# DomBoard.net
KiCad netlist of a schematic drawn in EAGLE
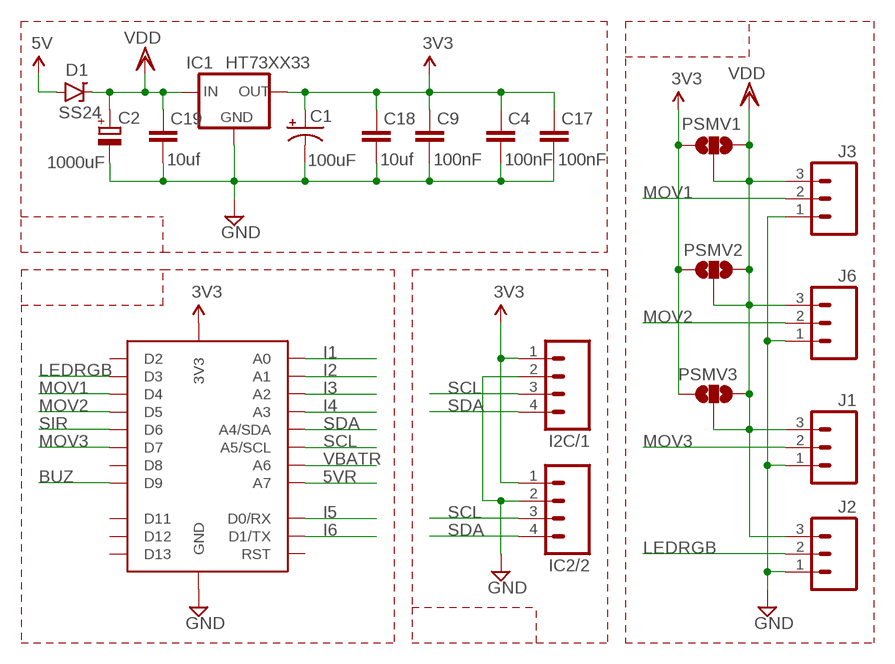
[diagram p0: schematic, sheet 1]
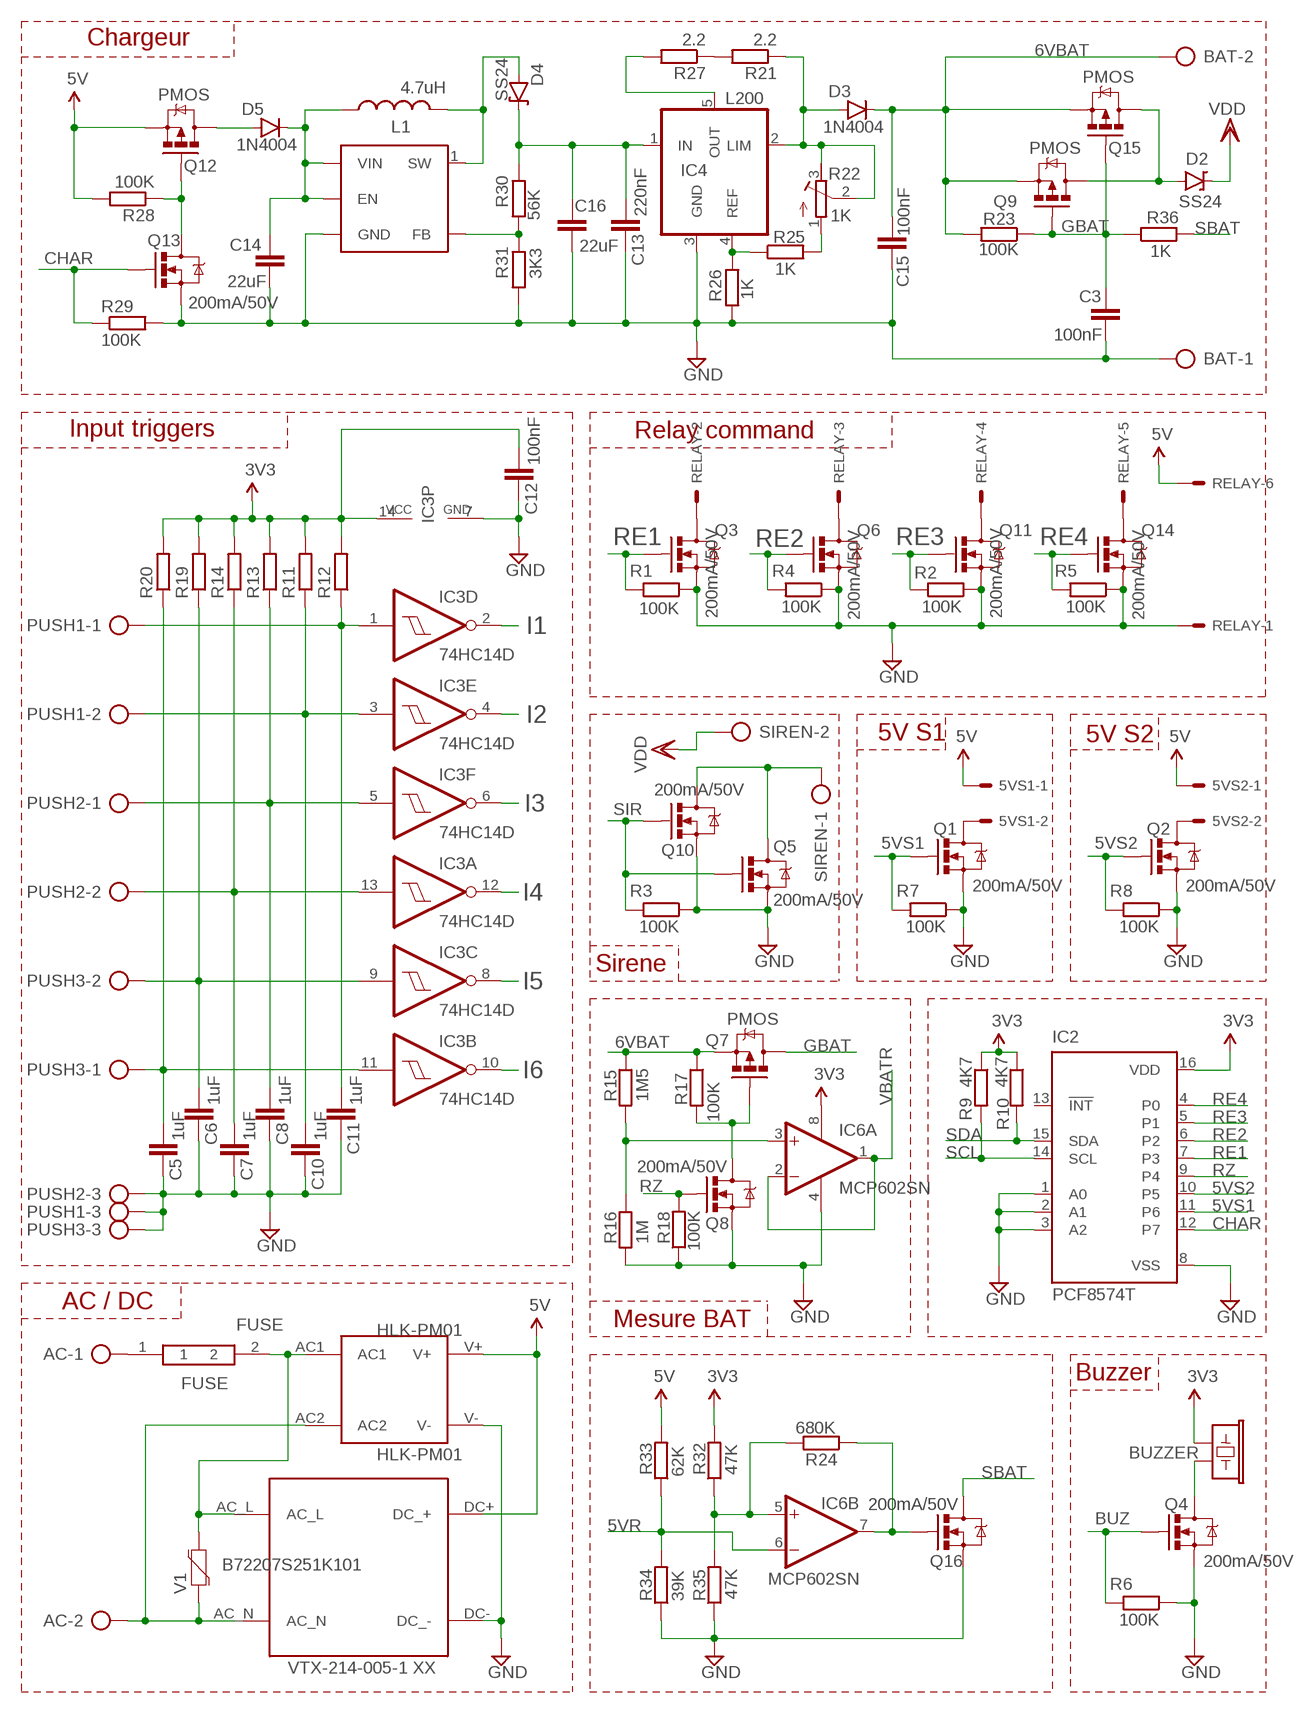
[diagram p1: schematic, sheet 2]

(export (version "E")
  (design (tool "Eeschema 10.0.6"))
  (components
    (comp (ref "C1")
      (value "100uF")
      (footprint "eagle-import:EIA3528-KIT")
      (libsource (lib "eagle-import") (part "CAP_POL3528-KIT"))
    )
    (comp (ref "C2")
      (value "1000uF")
      (footprint "eagle-import:E5-8,5")
      (libsource (lib "eagle-import") (part "CPOL-EUE5-8.5"))
    )
    (comp (ref "C4")
      (value "100nF")
      (footprint "eagle-import:C0805K")
      (libsource (lib "eagle-import") (part "C-EUC0805K"))
    )
    (comp (ref "C9")
      (value "100nF")
      (footprint "eagle-import:C0805K")
      (libsource (lib "eagle-import") (part "C-EUC0805K"))
    )
    (comp (ref "C17")
      (value "100nF")
      (footprint "eagle-import:C0805K")
      (libsource (lib "eagle-import") (part "C-EUC0805K"))
    )
    (comp (ref "C18")
      (value "10uf")
      (footprint "eagle-import:C0805K")
      (libsource (lib "eagle-import") (part "C-EUC0805K"))
    )
    (comp (ref "C19")
      (value "10uf")
      (footprint "eagle-import:C0805K")
      (libsource (lib "eagle-import") (part "C-EUC0805K"))
    )
    (comp (ref "D1")
      (value "SS24")
      (footprint "eagle-import:DO-214AA(1)")
      (libsource (lib "eagle-import") (part "SS24"))
    )
    (comp (ref "I2C/1")
      (value "M04PTH")
      (footprint "eagle-import:1X04")
      (libsource (lib "eagle-import") (part "M04PTH"))
    )
    (comp (ref "IC1")
      (value "HT73XX33")
      (footprint "eagle-import:SOT-89")
      (libsource (lib "eagle-import") (part "HT73XX33"))
    )
    (comp (ref "IC2/2")
      (value "M04PTH")
      (footprint "eagle-import:1X04")
      (libsource (lib "eagle-import") (part "M04PTH"))
    )
    (comp (ref "J1")
      (value "M03JST-PTH-VERT")
      (footprint "eagle-import:JST-3-PTH-VERT")
      (libsource (lib "eagle-import") (part "M03JST-PTH-VERT"))
    )
    (comp (ref "J2")
      (value "M03JST-PTH-VERT")
      (footprint "eagle-import:JST-3-PTH-VERT")
      (libsource (lib "eagle-import") (part "M03JST-PTH-VERT"))
    )
    (comp (ref "J3")
      (value "M03JST-PTH-VERT")
      (footprint "eagle-import:JST-3-PTH-VERT")
      (libsource (lib "eagle-import") (part "M03JST-PTH-VERT"))
    )
    (comp (ref "J6")
      (value "M03JST-PTH-VERT")
      (footprint "eagle-import:JST-3-PTH-VERT")
      (libsource (lib "eagle-import") (part "M03JST-PTH-VERT"))
    )
    (comp (ref "PROMINI69")
      (value "PROMINI69")
      (footprint "eagle-import:PROMINI69")
      (libsource (lib "eagle-import") (part "PROMINI69"))
    )
    (comp (ref "PSMV1")
      (value "JUMPER-PAD-3-NC_BY_TRACE")
      (footprint "eagle-import:PAD-JUMPER-3-3OF3_NC_BY_TRACE_YES_SILK_FULL_BOX")
      (libsource (lib "eagle-import") (part "JUMPER-PAD-3-NC_BY_TRACE"))
    )
    (comp (ref "PSMV2")
      (value "JUMPER-PAD-3-NC_BY_TRACE")
      (footprint "eagle-import:PAD-JUMPER-3-3OF3_NC_BY_TRACE_YES_SILK_FULL_BOX")
      (libsource (lib "eagle-import") (part "JUMPER-PAD-3-NC_BY_TRACE"))
    )
    (comp (ref "PSMV3")
      (value "JUMPER-PAD-3-NC_BY_TRACE")
      (footprint "eagle-import:PAD-JUMPER-3-3OF3_NC_BY_TRACE_YES_SILK_FULL_BOX")
      (libsource (lib "eagle-import") (part "JUMPER-PAD-3-NC_BY_TRACE"))
    )
    (comp (ref "5VS1")
      (value "22-23-2021")
      (footprint "eagle-import:22-23-2021")
      (fields (field (name "MF") "MOLEX"))
      (libsource (lib "eagle-import") (part "22-23-2021"))
    )
    (comp (ref "5VS2")
      (value "22-23-2021")
      (footprint "eagle-import:22-23-2021")
      (fields (field (name "MF") "MOLEX"))
      (libsource (lib "eagle-import") (part "22-23-2021"))
    )
    (comp (ref "AC")
      (value "AK500/2")
      (footprint "eagle-import:AK500_2")
      (libsource (lib "eagle-import") (part "AK500/2"))
    )
    (comp (ref "BAT")
      (value "AK500/2")
      (footprint "eagle-import:AK500_2")
      (libsource (lib "eagle-import") (part "AK500/2"))
    )
    (comp (ref "BUZZER")
      (value "BUZZER")
      (footprint "eagle-import:BUZZER-12MM")
      (libsource (lib "eagle-import") (part "BUZZERPTH"))
    )
    (comp (ref "C3")
      (value "100nF")
      (footprint "eagle-import:C0805K")
      (libsource (lib "eagle-import") (part "C-EUC0805K"))
    )
    (comp (ref "C5")
      (value "1uF")
      (footprint "eagle-import:C0805K")
      (libsource (lib "eagle-import") (part "C-EUC0805K"))
    )
    (comp (ref "C6")
      (value "1uF")
      (footprint "eagle-import:C0805K")
      (libsource (lib "eagle-import") (part "C-EUC0805K"))
    )
    (comp (ref "C7")
      (value "1uF")
      (footprint "eagle-import:C0805K")
      (libsource (lib "eagle-import") (part "C-EUC0805K"))
    )
    (comp (ref "C8")
      (value "1uF")
      (footprint "eagle-import:C0805K")
      (libsource (lib "eagle-import") (part "C-EUC0805K"))
    )
    (comp (ref "C10")
      (value "1uF")
      (footprint "eagle-import:C0805K")
      (libsource (lib "eagle-import") (part "C-EUC0805K"))
    )
    (comp (ref "C11")
      (value "1uF")
      (footprint "eagle-import:C0805K")
      (libsource (lib "eagle-import") (part "C-EUC0805K"))
    )
    (comp (ref "C12")
      (value "100nF")
      (footprint "eagle-import:C0805K")
      (libsource (lib "eagle-import") (part "C-EUC0805K"))
    )
    (comp (ref "C13")
      (value "220nF")
      (footprint "eagle-import:C0805K")
      (libsource (lib "eagle-import") (part "C-EUC0805K"))
    )
    (comp (ref "C14")
      (value "22uF")
      (footprint "eagle-import:C0805K")
      (libsource (lib "eagle-import") (part "C-EUC0805K"))
    )
    (comp (ref "C15")
      (value "100nF")
      (footprint "eagle-import:C0805K")
      (libsource (lib "eagle-import") (part "C-EUC0805K"))
    )
    (comp (ref "C16")
      (value "22uF")
      (footprint "eagle-import:C0805K")
      (libsource (lib "eagle-import") (part "C-EUC0805K"))
    )
    (comp (ref "D2")
      (value "SS24")
      (footprint "eagle-import:DO-214AA(1)")
      (libsource (lib "eagle-import") (part "SS24"))
    )
    (comp (ref "D3")
      (value "1N4004")
      (footprint "eagle-import:DO-214AA(1)")
      (libsource (lib "eagle-import") (part "DIODE"))
    )
    (comp (ref "D4")
      (value "SS24")
      (footprint "eagle-import:DO-214AA(1)")
      (libsource (lib "eagle-import") (part "SS24"))
    )
    (comp (ref "D5")
      (value "1N4004")
      (footprint "eagle-import:DO-214AA(1)")
      (libsource (lib "eagle-import") (part "DIODE"))
    )
    (comp (ref "FUSE")
      (value "FUSE")
      (footprint "eagle-import:FUSE_BEL_RST5_5A")
      (libsource (lib "eagle-import") (part "FUSE"))
    )
    (comp (ref "HLK-PM01")
      (value "HLK-PM01")
      (footprint "eagle-import:HILINK_HLK-PM01")
      (libsource (lib "eagle-import") (part "HILINK_HLK-PM01"))
    )
    (comp (ref "IC2")
      (value "PCF8574T")
      (footprint "eagle-import:SO16W")
      (fields (field (name "MPN") "PCF8574T/3,512"))
      (libsource (lib "eagle-import") (part "PCF8574T"))
    )
    (comp (ref "IC3")
      (value "74HC14D")
      (footprint "eagle-import:SO14")
      (libsource (lib "eagle-import") (part "7414DHC"))
    )
    (comp (ref "IC4")
      (value "L200")
      (footprint "eagle-import:L200S")
      (libsource (lib "eagle-import") (part "L200"))
    )
    (comp (ref "IC5")
      (value "SX1308")
      (footprint "eagle-import:SOT23-6")
      (libsource (lib "eagle-import") (part "SX1308"))
    )
    (comp (ref "IC6")
      (value "MCP602SN")
      (footprint "eagle-import:SO08")
      (libsource (lib "eagle-import") (part "MCP602SN"))
    )
    (comp (ref "L1")
      (value "4.7uH")
      (footprint "eagle-import:INDUC1")
      (libsource (lib "eagle-import") (part "INDUCTOR"))
    )
    (comp (ref "PUSH1")
      (value "AK500/3")
      (footprint "eagle-import:AK500_3")
      (libsource (lib "eagle-import") (part "AK500/3"))
    )
    (comp (ref "PUSH2")
      (value "AK500/3")
      (footprint "eagle-import:AK500_3")
      (libsource (lib "eagle-import") (part "AK500/3"))
    )
    (comp (ref "PUSH3")
      (value "AK500/3")
      (footprint "eagle-import:AK500_3")
      (libsource (lib "eagle-import") (part "AK500/3"))
    )
    (comp (ref "Q1")
      (value "200mA/50V")
      (footprint "eagle-import:SOT23-3")
      (libsource (lib "eagle-import") (part "N-MOSFETBSS138"))
    )
    (comp (ref "Q2")
      (value "200mA/50V")
      (footprint "eagle-import:SOT23-3")
      (libsource (lib "eagle-import") (part "N-MOSFETBSS138"))
    )
    (comp (ref "Q3")
      (value "200mA/50V")
      (footprint "eagle-import:SOT23-3")
      (libsource (lib "eagle-import") (part "N-MOSFETBSS138"))
    )
    (comp (ref "Q4")
      (value "200mA/50V")
      (footprint "eagle-import:SOT23-3")
      (libsource (lib "eagle-import") (part "N-MOSFETBSS138"))
    )
    (comp (ref "Q5")
      (value "200mA/50V")
      (footprint "eagle-import:SOT23-3")
      (libsource (lib "eagle-import") (part "N-MOSFETBSS138"))
    )
    (comp (ref "Q6")
      (value "200mA/50V")
      (footprint "eagle-import:SOT23-3")
      (libsource (lib "eagle-import") (part "N-MOSFETBSS138"))
    )
    (comp (ref "Q7")
      (value "PMOS")
      (footprint "eagle-import:SOT23-3")
      (libsource (lib "eagle-import") (part "P-MOSFET"))
    )
    (comp (ref "Q8")
      (value "200mA/50V")
      (footprint "eagle-import:SOT23-3")
      (libsource (lib "eagle-import") (part "N-MOSFETBSS138"))
    )
    (comp (ref "Q9")
      (value "PMOS")
      (footprint "eagle-import:SOT23-3")
      (libsource (lib "eagle-import") (part "P-MOSFET"))
    )
    (comp (ref "Q10")
      (value "200mA/50V")
      (footprint "eagle-import:SOT23-3")
      (libsource (lib "eagle-import") (part "N-MOSFETBSS138"))
    )
    (comp (ref "Q11")
      (value "200mA/50V")
      (footprint "eagle-import:SOT23-3")
      (libsource (lib "eagle-import") (part "N-MOSFETBSS138"))
    )
    (comp (ref "Q12")
      (value "PMOS")
      (footprint "eagle-import:SOT23-3")
      (libsource (lib "eagle-import") (part "P-MOSFET"))
    )
    (comp (ref "Q13")
      (value "200mA/50V")
      (footprint "eagle-import:SOT23-3")
      (libsource (lib "eagle-import") (part "N-MOSFETBSS138"))
    )
    (comp (ref "Q14")
      (value "200mA/50V")
      (footprint "eagle-import:SOT23-3")
      (libsource (lib "eagle-import") (part "N-MOSFETBSS138"))
    )
    (comp (ref "Q15")
      (value "PMOS")
      (footprint "eagle-import:SOT23-3")
      (libsource (lib "eagle-import") (part "P-MOSFET"))
    )
    (comp (ref "Q16")
      (value "200mA/50V")
      (footprint "eagle-import:SOT23-3")
      (libsource (lib "eagle-import") (part "N-MOSFETBSS138"))
    )
    (comp (ref "R1")
      (value "100K")
      (footprint "eagle-import:R0805")
      (libsource (lib "eagle-import") (part "R-EUR0805"))
    )
    (comp (ref "R2")
      (value "100K")
      (footprint "eagle-import:R0805")
      (libsource (lib "eagle-import") (part "R-EUR0805"))
    )
    (comp (ref "R3")
      (value "100K")
      (footprint "eagle-import:R0805")
      (libsource (lib "eagle-import") (part "R-EUR0805"))
    )
    (comp (ref "R4")
      (value "100K")
      (footprint "eagle-import:R0805")
      (libsource (lib "eagle-import") (part "R-EUR0805"))
    )
    (comp (ref "R5")
      (value "100K")
      (footprint "eagle-import:R0805")
      (libsource (lib "eagle-import") (part "R-EUR0805"))
    )
    (comp (ref "R6")
      (value "100K")
      (footprint "eagle-import:R0805")
      (libsource (lib "eagle-import") (part "R-EUR0805"))
    )
    (comp (ref "R7")
      (value "100K")
      (footprint "eagle-import:R0805")
      (libsource (lib "eagle-import") (part "R-EUR0805"))
    )
    (comp (ref "R8")
      (value "100K")
      (footprint "eagle-import:R0805")
      (libsource (lib "eagle-import") (part "R-EUR0805"))
    )
    (comp (ref "R9")
      (value "4K7")
      (footprint "eagle-import:R0805")
      (libsource (lib "eagle-import") (part "R-EUR0805"))
    )
    (comp (ref "R10")
      (value "4K7")
      (footprint "eagle-import:R0805")
      (libsource (lib "eagle-import") (part "R-EUR0805"))
    )
    (comp (ref "R11")
      (value "R-EUR0805")
      (footprint "eagle-import:R0805")
      (libsource (lib "eagle-import") (part "R-EUR0805"))
    )
    (comp (ref "R12")
      (value "R-EUR0805")
      (footprint "eagle-import:R0805")
      (libsource (lib "eagle-import") (part "R-EUR0805"))
    )
    (comp (ref "R13")
      (value "R-EUR0805")
      (footprint "eagle-import:R0805")
      (libsource (lib "eagle-import") (part "R-EUR0805"))
    )
    (comp (ref "R14")
      (value "R-EUR0805")
      (footprint "eagle-import:R0805")
      (libsource (lib "eagle-import") (part "R-EUR0805"))
    )
    (comp (ref "R15")
      (value "1M5")
      (footprint "eagle-import:R0805")
      (libsource (lib "eagle-import") (part "R-EUR0805"))
    )
    (comp (ref "R16")
      (value "1M")
      (footprint "eagle-import:R0805")
      (libsource (lib "eagle-import") (part "R-EUR0805"))
    )
    (comp (ref "R17")
      (value "100K")
      (footprint "eagle-import:R0805")
      (libsource (lib "eagle-import") (part "R-EUR0805"))
    )
    (comp (ref "R18")
      (value "100K")
      (footprint "eagle-import:R0805")
      (libsource (lib "eagle-import") (part "R-EUR0805"))
    )
    (comp (ref "R19")
      (value "R-EUR0805")
      (footprint "eagle-import:R0805")
      (libsource (lib "eagle-import") (part "R-EUR0805"))
    )
    (comp (ref "R20")
      (value "R-EUR0805")
      (footprint "eagle-import:R0805")
      (libsource (lib "eagle-import") (part "R-EUR0805"))
    )
    (comp (ref "R21")
      (value "2.2")
      (footprint "eagle-import:R0805")
      (libsource (lib "eagle-import") (part "R-EUR0805"))
    )
    (comp (ref "R22")
      (value "1K")
      (footprint "eagle-import:RTRIM3296W")
      (libsource (lib "eagle-import") (part "R-TRIMM3296W"))
    )
    (comp (ref "R23")
      (value "100K")
      (footprint "eagle-import:R0805")
      (libsource (lib "eagle-import") (part "R-EUR0805"))
    )
    (comp (ref "R24")
      (value "680K")
      (footprint "eagle-import:R0805")
      (libsource (lib "eagle-import") (part "R-EUR0805"))
    )
    (comp (ref "R25")
      (value "1K")
      (footprint "eagle-import:R0805")
      (libsource (lib "eagle-import") (part "R-EUR0805"))
    )
    (comp (ref "R26")
      (value "1K")
      (footprint "eagle-import:R0805")
      (libsource (lib "eagle-import") (part "R-EUR0805"))
    )
    (comp (ref "R27")
      (value "2.2")
      (footprint "eagle-import:R0805")
      (libsource (lib "eagle-import") (part "R-EUR0805"))
    )
    (comp (ref "R28")
      (value "100K")
      (footprint "eagle-import:R0805")
      (libsource (lib "eagle-import") (part "R-EUR0805"))
    )
    (comp (ref "R29")
      (value "100K")
      (footprint "eagle-import:R0805")
      (libsource (lib "eagle-import") (part "R-EUR0805"))
    )
    (comp (ref "R30")
      (value "56K")
      (footprint "eagle-import:M0805")
      (libsource (lib "eagle-import") (part "R-EUM0805"))
    )
    (comp (ref "R31")
      (value "3K3")
      (footprint "eagle-import:M0805")
      (libsource (lib "eagle-import") (part "R-EUM0805"))
    )
    (comp (ref "R32")
      (value "47K")
      (footprint "eagle-import:R0805")
      (libsource (lib "eagle-import") (part "R-EUR0805"))
    )
    (comp (ref "R33")
      (value "62K")
      (footprint "eagle-import:R0805")
      (libsource (lib "eagle-import") (part "R-EUR0805"))
    )
    (comp (ref "R34")
      (value "39K")
      (footprint "eagle-import:R0805")
      (libsource (lib "eagle-import") (part "R-EUR0805"))
    )
    (comp (ref "R35")
      (value "47K")
      (footprint "eagle-import:R0805")
      (libsource (lib "eagle-import") (part "R-EUR0805"))
    )
    (comp (ref "R36")
      (value "1K")
      (footprint "eagle-import:R0805")
      (libsource (lib "eagle-import") (part "R-EUR0805"))
    )
    (comp (ref "RELAY")
      (value "22-23-2061")
      (footprint "eagle-import:22-23-2061")
      (fields (field (name "MF") "MOLEX"))
      (libsource (lib "eagle-import") (part "22-23-2061"))
    )
    (comp (ref "SIREN")
      (value "AK500/2")
      (footprint "eagle-import:AK500_2")
      (libsource (lib "eagle-import") (part "AK500/2"))
    )
    (comp (ref "V1")
      (value "B72207S251K101")
      (footprint "eagle-import:VARISTOR_B72207S251K101")
      (libsource (lib "eagle-import") (part "VARISTOR_B72207S251K101"))
    )
    (comp (ref "VTX1")
      (value "VTX-214-005-1XX")
      (footprint "eagle-import:VTX-214-005-1XX")
      (libsource (lib "eagle-import") (part "VTX-214-005-1XX"))
    )
  )
  (nets
    (net (code "1") (name "3.3V") (class "Default")
      (node (ref "BUZZER") (pin "+") (pinfunction "1_+") (pintype "passive"))
      (node (ref "C1") (pin "A") (pinfunction "+_A") (pintype "passive"))
      (node (ref "C12") (pin "1") (pinfunction "1_1") (pintype "passive"))
      (node (ref "C17") (pin "2") (pinfunction "2_2") (pintype "passive"))
      (node (ref "C18") (pin "2") (pinfunction "2_2") (pintype "passive"))
      (node (ref "C4") (pin "2") (pinfunction "2_2") (pintype "passive"))
      (node (ref "C9") (pin "2") (pinfunction "2_2") (pintype "passive"))
      (node (ref "I2C/1") (pin "1") (pinfunction "1_1") (pintype "passive"))
      (node (ref "IC1") (pin "1") (pinfunction "OUT_1") (pintype "passive"))
      (node (ref "IC2") (pin "16") (pinfunction "VDD_16") (pintype "power_in"))
      (node (ref "IC2/2") (pin "1") (pinfunction "1_1") (pintype "passive"))
      (node (ref "IC3") (pin "14") (pinfunction "VCC_14") (pintype "power_in"))
      (node (ref "IC6") (pin "8") (pinfunction "V+_8") (pintype "power_in"))
      (node (ref "PROMINI69") (pin "3V3") (pinfunction "3V3_3V3") (pintype "power_in"))
      (node (ref "PSMV1") (pin "1") (pinfunction "1_1") (pintype "passive"))
      (node (ref "PSMV2") (pin "1") (pinfunction "1_1") (pintype "passive"))
      (node (ref "PSMV3") (pin "1") (pinfunction "1_1") (pintype "passive"))
      (node (ref "R10") (pin "1") (pinfunction "1_1") (pintype "passive"))
      (node (ref "R11") (pin "2") (pinfunction "2_2") (pintype "passive"))
      (node (ref "R12") (pin "2") (pinfunction "2_2") (pintype "passive"))
      (node (ref "R13") (pin "2") (pinfunction "2_2") (pintype "passive"))
      (node (ref "R14") (pin "2") (pinfunction "2_2") (pintype "passive"))
      (node (ref "R19") (pin "2") (pinfunction "2_2") (pintype "passive"))
      (node (ref "R20") (pin "2") (pinfunction "2_2") (pintype "passive"))
      (node (ref "R32") (pin "2") (pinfunction "2_2") (pintype "passive"))
      (node (ref "R9") (pin "1") (pinfunction "1_1") (pintype "passive"))
    )
    (net (code "2") (name "5V") (class "Default")
      (node (ref "5VS1") (pin "1") (pinfunction "S_1") (pintype "passive"))
      (node (ref "5VS2") (pin "1") (pinfunction "S_1") (pintype "passive"))
      (node (ref "D1") (pin "A") (pinfunction "A_A") (pintype "passive"))
      (node (ref "HLK-PM01") (pin "V+") (pinfunction "V+_V+") (pintype "bidirectional"))
      (node (ref "Q12") (pin "2") (pinfunction "S_2") (pintype "passive"))
      (node (ref "R28") (pin "2") (pinfunction "2_2") (pintype "passive"))
      (node (ref "R33") (pin "2") (pinfunction "2_2") (pintype "passive"))
      (node (ref "RELAY") (pin "6") (pinfunction "S_6") (pintype "passive"))
      (node (ref "VTX1") (pin "DC+") (pinfunction "DC_+_DC+") (pintype "power_in"))
    )
    (net (code "3") (name "5VR") (class "Default")
      (node (ref "IC6") (pin "6") (pinfunction "-IN_6") (pintype "input"))
      (node (ref "PROMINI69") (pin "A7") (pinfunction "A7_A7") (pintype "bidirectional"))
      (node (ref "R33") (pin "1") (pinfunction "1_1") (pintype "passive"))
      (node (ref "R34") (pin "2") (pinfunction "2_2") (pintype "passive"))
    )
    (net (code "4") (name "5VS1") (class "Default")
      (node (ref "IC2") (pin "11") (pinfunction "P6_11") (pintype "bidirectional"))
      (node (ref "Q1") (pin "1") (pinfunction "G_1") (pintype "passive"))
      (node (ref "R7") (pin "2") (pinfunction "2_2") (pintype "passive"))
    )
    (net (code "5") (name "5VS2") (class "Default")
      (node (ref "IC2") (pin "10") (pinfunction "P5_10") (pintype "bidirectional"))
      (node (ref "Q2") (pin "1") (pinfunction "G_1") (pintype "passive"))
      (node (ref "R8") (pin "2") (pinfunction "2_2") (pintype "passive"))
    )
    (net (code "6") (name "6VBAT") (class "Default")
      (node (ref "BAT") (pin "2") (pinfunction "KL_2") (pintype "passive"))
      (node (ref "C15") (pin "1") (pinfunction "1_1") (pintype "passive"))
      (node (ref "D3") (pin "C") (pinfunction "C_C") (pintype "passive"))
      (node (ref "Q15") (pin "2") (pinfunction "S_2") (pintype "passive"))
      (node (ref "Q7") (pin "2") (pinfunction "S_2") (pintype "passive"))
      (node (ref "Q9") (pin "2") (pinfunction "S_2") (pintype "passive"))
      (node (ref "R15") (pin "1") (pinfunction "1_1") (pintype "passive"))
      (node (ref "R17") (pin "1") (pinfunction "1_1") (pintype "passive"))
      (node (ref "R23") (pin "2") (pinfunction "2_2") (pintype "passive"))
    )
    (net (code "7") (name "BUZ") (class "Default")
      (node (ref "PROMINI69") (pin "D9") (pinfunction "D9_D9") (pintype "bidirectional"))
      (node (ref "Q4") (pin "1") (pinfunction "G_1") (pintype "passive"))
      (node (ref "R6") (pin "2") (pinfunction "2_2") (pintype "passive"))
    )
    (net (code "8") (name "CHAR") (class "Default")
      (node (ref "IC2") (pin "12") (pinfunction "P7_12") (pintype "bidirectional"))
      (node (ref "Q13") (pin "1") (pinfunction "G_1") (pintype "passive"))
      (node (ref "R29") (pin "1") (pinfunction "1_1") (pintype "passive"))
    )
    (net (code "9") (name "GBAT") (class "Default")
      (node (ref "C3") (pin "1") (pinfunction "1_1") (pintype "passive"))
      (node (ref "Q15") (pin "1") (pinfunction "G_1") (pintype "passive"))
      (node (ref "Q7") (pin "3") (pinfunction "D_3") (pintype "passive"))
      (node (ref "Q9") (pin "1") (pinfunction "G_1") (pintype "passive"))
      (node (ref "R23") (pin "1") (pinfunction "1_1") (pintype "passive"))
      (node (ref "R36") (pin "1") (pinfunction "1_1") (pintype "passive"))
    )
    (net (code "10") (name "GND") (class "Default")
      (node (ref "BAT") (pin "1") (pinfunction "KL_1") (pintype "passive"))
      (node (ref "C1") (pin "C") (pinfunction "-_C") (pintype "passive"))
      (node (ref "C10") (pin "2") (pinfunction "2_2") (pintype "passive"))
      (node (ref "C11") (pin "2") (pinfunction "2_2") (pintype "passive"))
      (node (ref "C12") (pin "2") (pinfunction "2_2") (pintype "passive"))
      (node (ref "C13") (pin "2") (pinfunction "2_2") (pintype "passive"))
      (node (ref "C14") (pin "2") (pinfunction "2_2") (pintype "passive"))
      (node (ref "C15") (pin "2") (pinfunction "2_2") (pintype "passive"))
      (node (ref "C16") (pin "2") (pinfunction "2_2") (pintype "passive"))
      (node (ref "C17") (pin "1") (pinfunction "1_1") (pintype "passive"))
      (node (ref "C18") (pin "1") (pinfunction "1_1") (pintype "passive"))
      (node (ref "C19") (pin "1") (pinfunction "1_1") (pintype "passive"))
      (node (ref "C2") (pin "-") (pinfunction "-_-") (pintype "passive"))
      (node (ref "C3") (pin "2") (pinfunction "2_2") (pintype "passive"))
      (node (ref "C4") (pin "1") (pinfunction "1_1") (pintype "passive"))
      (node (ref "C5") (pin "2") (pinfunction "2_2") (pintype "passive"))
      (node (ref "C6") (pin "2") (pinfunction "2_2") (pintype "passive"))
      (node (ref "C7") (pin "2") (pinfunction "2_2") (pintype "passive"))
      (node (ref "C8") (pin "2") (pinfunction "2_2") (pintype "passive"))
      (node (ref "C9") (pin "1") (pinfunction "1_1") (pintype "passive"))
      (node (ref "HLK-PM01") (pin "V-") (pinfunction "V-_V-") (pintype "bidirectional"))
      (node (ref "I2C/1") (pin "2") (pinfunction "2_2") (pintype "passive"))
      (node (ref "IC1") (pin "2") (pinfunction "GND_2") (pintype "input"))
      (node (ref "IC2") (pin "1") (pinfunction "A0_1") (pintype "input"))
      (node (ref "IC2") (pin "2") (pinfunction "A1_2") (pintype "input"))
      (node (ref "IC2") (pin "3") (pinfunction "A2_3") (pintype "input"))
      (node (ref "IC2") (pin "8") (pinfunction "VSS_8") (pintype "power_in"))
      (node (ref "IC2/2") (pin "2") (pinfunction "2_2") (pintype "passive"))
      (node (ref "IC3") (pin "7") (pinfunction "GND_7") (pintype "power_in"))
      (node (ref "IC4") (pin "3") (pinfunction "GND_3") (pintype "passive"))
      (node (ref "IC5") (pin "2") (pinfunction "GND_2") (pintype "power_in"))
      (node (ref "IC6") (pin "4") (pinfunction "V-_4") (pintype "power_in"))
      (node (ref "J1") (pin "1") (pinfunction "1_1") (pintype "passive"))
      (node (ref "J2") (pin "1") (pinfunction "1_1") (pintype "passive"))
      (node (ref "J3") (pin "1") (pinfunction "1_1") (pintype "passive"))
      (node (ref "J6") (pin "1") (pinfunction "1_1") (pintype "passive"))
      (node (ref "PROMINI69") (pin "GND") (pinfunction "GND_GND") (pintype "power_in"))
      (node (ref "PUSH1") (pin "3") (pinfunction "KL_3") (pintype "passive"))
      (node (ref "PUSH2") (pin "3") (pinfunction "KL_3") (pintype "passive"))
      (node (ref "PUSH3") (pin "3") (pinfunction "KL_3") (pintype "passive"))
      (node (ref "Q1") (pin "2") (pinfunction "S_2") (pintype "passive"))
      (node (ref "Q10") (pin "2") (pinfunction "S_2") (pintype "passive"))
      (node (ref "Q11") (pin "2") (pinfunction "S_2") (pintype "passive"))
      (node (ref "Q13") (pin "2") (pinfunction "S_2") (pintype "passive"))
      (node (ref "Q14") (pin "2") (pinfunction "S_2") (pintype "passive"))
      (node (ref "Q16") (pin "2") (pinfunction "S_2") (pintype "passive"))
      (node (ref "Q2") (pin "2") (pinfunction "S_2") (pintype "passive"))
      (node (ref "Q3") (pin "2") (pinfunction "S_2") (pintype "passive"))
      (node (ref "Q4") (pin "2") (pinfunction "S_2") (pintype "passive"))
      (node (ref "Q5") (pin "2") (pinfunction "S_2") (pintype "passive"))
      (node (ref "Q6") (pin "2") (pinfunction "S_2") (pintype "passive"))
      (node (ref "Q8") (pin "2") (pinfunction "S_2") (pintype "passive"))
      (node (ref "R1") (pin "1") (pinfunction "1_1") (pintype "passive"))
      (node (ref "R16") (pin "2") (pinfunction "2_2") (pintype "passive"))
      (node (ref "R18") (pin "1") (pinfunction "1_1") (pintype "passive"))
      (node (ref "R2") (pin "1") (pinfunction "1_1") (pintype "passive"))
      (node (ref "R26") (pin "2") (pinfunction "2_2") (pintype "passive"))
      (node (ref "R29") (pin "2") (pinfunction "2_2") (pintype "passive"))
      (node (ref "R3") (pin "1") (pinfunction "1_1") (pintype "passive"))
      (node (ref "R31") (pin "1") (pinfunction "1_1") (pintype "passive"))
      (node (ref "R34") (pin "1") (pinfunction "1_1") (pintype "passive"))
      (node (ref "R35") (pin "1") (pinfunction "1_1") (pintype "passive"))
      (node (ref "R4") (pin "1") (pinfunction "1_1") (pintype "passive"))
      (node (ref "R5") (pin "1") (pinfunction "1_1") (pintype "passive"))
      (node (ref "R6") (pin "1") (pinfunction "1_1") (pintype "passive"))
      (node (ref "R7") (pin "1") (pinfunction "1_1") (pintype "passive"))
      (node (ref "R8") (pin "1") (pinfunction "1_1") (pintype "passive"))
      (node (ref "RELAY") (pin "1") (pinfunction "S_1") (pintype "passive"))
      (node (ref "VTX1") (pin "DC-") (pinfunction "DC_-_DC-") (pintype "power_in"))
    )
    (net (code "11") (name "I1") (class "Default")
      (node (ref "IC3") (pin "2") (pinfunction "O_2") (pintype "output"))
      (node (ref "PROMINI69") (pin "A0") (pinfunction "A0_A0") (pintype "bidirectional"))
    )
    (net (code "12") (name "I2") (class "Default")
      (node (ref "IC3") (pin "4") (pinfunction "O_4") (pintype "output"))
      (node (ref "PROMINI69") (pin "A1") (pinfunction "A1_A1") (pintype "bidirectional"))
    )
    (net (code "13") (name "I3") (class "Default")
      (node (ref "IC3") (pin "6") (pinfunction "O_6") (pintype "output"))
      (node (ref "PROMINI69") (pin "A2") (pinfunction "A2_A2") (pintype "bidirectional"))
    )
    (net (code "14") (name "I4") (class "Default")
      (node (ref "IC3") (pin "12") (pinfunction "O_12") (pintype "output"))
      (node (ref "PROMINI69") (pin "A3") (pinfunction "A3_A3") (pintype "bidirectional"))
    )
    (net (code "15") (name "I5") (class "Default")
      (node (ref "IC3") (pin "8") (pinfunction "O_8") (pintype "output"))
      (node (ref "PROMINI69") (pin "D0") (pinfunction "D0/RX_D0") (pintype "bidirectional"))
    )
    (net (code "16") (name "I6") (class "Default")
      (node (ref "IC3") (pin "10") (pinfunction "O_10") (pintype "output"))
      (node (ref "PROMINI69") (pin "D1") (pinfunction "D1/TX_D1") (pintype "bidirectional"))
    )
    (net (code "17") (name "LEDRGB") (class "Default")
      (node (ref "J2") (pin "2") (pinfunction "2_2") (pintype "passive"))
      (node (ref "PROMINI69") (pin "D3") (pinfunction "D3_D3") (pintype "bidirectional"))
    )
    (net (code "18") (name "MOV1") (class "Default")
      (node (ref "J3") (pin "2") (pinfunction "2_2") (pintype "passive"))
      (node (ref "PROMINI69") (pin "D4") (pinfunction "D4_D4") (pintype "bidirectional"))
    )
    (net (code "19") (name "MOV2") (class "Default")
      (node (ref "J6") (pin "2") (pinfunction "2_2") (pintype "passive"))
      (node (ref "PROMINI69") (pin "D5") (pinfunction "D5_D5") (pintype "bidirectional"))
    )
    (net (code "20") (name "MOV3") (class "Default")
      (node (ref "J1") (pin "2") (pinfunction "2_2") (pintype "passive"))
      (node (ref "PROMINI69") (pin "D7") (pinfunction "D7_D7") (pintype "bidirectional"))
    )
    (net (code "21") (name "Net-(5VS1B-S)") (class "Default")
      (node (ref "5VS1") (pin "2") (pinfunction "S_2") (pintype "passive"))
      (node (ref "Q1") (pin "3") (pinfunction "D_3") (pintype "passive"))
    )
    (net (code "22") (name "Net-(5VS2B-S)") (class "Default")
      (node (ref "5VS2") (pin "2") (pinfunction "S_2") (pintype "passive"))
      (node (ref "Q2") (pin "3") (pinfunction "D_3") (pintype "passive"))
    )
    (net (code "23") (name "Net-(ACA-KL)") (class "Default")
      (node (ref "AC") (pin "1") (pinfunction "KL_1") (pintype "passive"))
      (node (ref "FUSE") (pin "1") (pinfunction "1_1") (pintype "bidirectional"))
    )
    (net (code "24") (name "Net-(ACB-KL)") (class "Default")
      (node (ref "AC") (pin "2") (pinfunction "KL_2") (pintype "passive"))
      (node (ref "HLK-PM01") (pin "AC2") (pinfunction "AC2_AC2") (pintype "bidirectional"))
      (node (ref "V1") (pin "1") (pinfunction "1_1") (pintype "passive"))
      (node (ref "VTX1") (pin "AC_N") (pinfunction "AC_N_AC_N") (pintype "power_in"))
    )
    (net (code "25") (name "Net-(BUZZER-2)") (class "Default")
      (node (ref "BUZZER") (pin "-") (pinfunction "2_-") (pintype "passive"))
      (node (ref "Q4") (pin "3") (pinfunction "D_3") (pintype "passive"))
    )
    (net (code "26") (name "Net-(FUSE-Pad2)") (class "Default")
      (node (ref "FUSE") (pin "2") (pinfunction "2_2") (pintype "bidirectional"))
      (node (ref "HLK-PM01") (pin "AC1") (pinfunction "AC1_AC1") (pintype "bidirectional"))
      (node (ref "V1") (pin "2") (pinfunction "2_2") (pintype "passive"))
      (node (ref "VTX1") (pin "AC_L") (pinfunction "AC_L_AC_L") (pintype "power_in"))
    )
    (net (code "27") (name "Net-(IC3A-I)") (class "Default")
      (node (ref "C7") (pin "1") (pinfunction "1_1") (pintype "passive"))
      (node (ref "IC3") (pin "13") (pinfunction "I_13") (pintype "input"))
      (node (ref "PUSH2") (pin "2") (pinfunction "KL_2") (pintype "passive"))
      (node (ref "R14") (pin "1") (pinfunction "1_1") (pintype "passive"))
    )
    (net (code "28") (name "Net-(IC3B-I)") (class "Default")
      (node (ref "C5") (pin "1") (pinfunction "1_1") (pintype "passive"))
      (node (ref "IC3") (pin "11") (pinfunction "I_11") (pintype "input"))
      (node (ref "PUSH3") (pin "1") (pinfunction "KL_1") (pintype "passive"))
      (node (ref "R20") (pin "1") (pinfunction "1_1") (pintype "passive"))
    )
    (net (code "29") (name "Net-(IC3C-I)") (class "Default")
      (node (ref "C6") (pin "1") (pinfunction "1_1") (pintype "passive"))
      (node (ref "IC3") (pin "9") (pinfunction "I_9") (pintype "input"))
      (node (ref "PUSH3") (pin "2") (pinfunction "KL_2") (pintype "passive"))
      (node (ref "R19") (pin "1") (pinfunction "1_1") (pintype "passive"))
    )
    (net (code "30") (name "Net-(IC3D-I)") (class "Default")
      (node (ref "C11") (pin "1") (pinfunction "1_1") (pintype "passive"))
      (node (ref "IC3") (pin "1") (pinfunction "I_1") (pintype "input"))
      (node (ref "PUSH1") (pin "1") (pinfunction "KL_1") (pintype "passive"))
      (node (ref "R12") (pin "1") (pinfunction "1_1") (pintype "passive"))
    )
    (net (code "31") (name "Net-(IC3E-I)") (class "Default")
      (node (ref "C10") (pin "1") (pinfunction "1_1") (pintype "passive"))
      (node (ref "IC3") (pin "3") (pinfunction "I_3") (pintype "input"))
      (node (ref "PUSH1") (pin "2") (pinfunction "KL_2") (pintype "passive"))
      (node (ref "R11") (pin "1") (pinfunction "1_1") (pintype "passive"))
    )
    (net (code "32") (name "Net-(IC3F-I)") (class "Default")
      (node (ref "C8") (pin "1") (pinfunction "1_1") (pintype "passive"))
      (node (ref "IC3") (pin "5") (pinfunction "I_5") (pintype "input"))
      (node (ref "PUSH2") (pin "1") (pinfunction "KL_1") (pintype "passive"))
      (node (ref "R13") (pin "1") (pinfunction "1_1") (pintype "passive"))
    )
    (net (code "33") (name "Net-(IC4-IN)") (class "Default")
      (node (ref "C13") (pin "1") (pinfunction "1_1") (pintype "passive"))
      (node (ref "C16") (pin "1") (pinfunction "1_1") (pintype "passive"))
      (node (ref "D4") (pin "C") (pinfunction "C_C") (pintype "passive"))
      (node (ref "IC4") (pin "1") (pinfunction "IN_1") (pintype "input"))
      (node (ref "R30") (pin "2") (pinfunction "2_2") (pintype "passive"))
    )
    (net (code "34") (name "Net-(IC4-LIM)") (class "Default")
      (node (ref "D3") (pin "A") (pinfunction "A_A") (pintype "passive"))
      (node (ref "IC4") (pin "2") (pinfunction "LIM_2") (pintype "input"))
      (node (ref "R21") (pin "1") (pinfunction "1_1") (pintype "passive"))
      (node (ref "R22") (pin "2") (pinfunction "S_2") (pintype "passive"))
      (node (ref "R22") (pin "3") (pinfunction "E_3") (pintype "passive"))
    )
    (net (code "35") (name "Net-(IC4-OUT)") (class "Default")
      (node (ref "IC4") (pin "5") (pinfunction "OUT_5") (pintype "passive"))
      (node (ref "R27") (pin "2") (pinfunction "2_2") (pintype "passive"))
    )
    (net (code "36") (name "Net-(IC4-REF)") (class "Default")
      (node (ref "IC4") (pin "4") (pinfunction "REF_4") (pintype "input"))
      (node (ref "R25") (pin "1") (pinfunction "1_1") (pintype "passive"))
      (node (ref "R26") (pin "1") (pinfunction "1_1") (pintype "passive"))
    )
    (net (code "37") (name "Net-(IC5-EN)") (class "Default")
      (node (ref "C14") (pin "1") (pinfunction "1_1") (pintype "passive"))
      (node (ref "D5") (pin "C") (pinfunction "C_C") (pintype "passive"))
      (node (ref "IC5") (pin "4") (pinfunction "EN_4") (pintype "bidirectional"))
      (node (ref "IC5") (pin "5") (pinfunction "VIN_5") (pintype "power_in"))
      (node (ref "L1") (pin "1") (pinfunction "1_1") (pintype "passive"))
    )
    (net (code "38") (name "Net-(IC5-FB)") (class "Default")
      (node (ref "IC5") (pin "3") (pinfunction "FB_3") (pintype "bidirectional"))
      (node (ref "R30") (pin "1") (pinfunction "1_1") (pintype "passive"))
      (node (ref "R31") (pin "2") (pinfunction "2_2") (pintype "passive"))
    )
    (net (code "39") (name "Net-(IC5-SW)") (class "Default")
      (node (ref "D4") (pin "A") (pinfunction "A_A") (pintype "passive"))
      (node (ref "IC5") (pin "1") (pinfunction "SW_1") (pintype "bidirectional"))
      (node (ref "L1") (pin "2") (pinfunction "2_2") (pintype "passive"))
    )
    (net (code "40") (name "Net-(IC6A-+IN)") (class "Default")
      (node (ref "IC6") (pin "3") (pinfunction "+IN_3") (pintype "input"))
      (node (ref "R15") (pin "2") (pinfunction "2_2") (pintype "passive"))
      (node (ref "R16") (pin "1") (pinfunction "1_1") (pintype "passive"))
    )
    (net (code "41") (name "Net-(IC6B-+IN)") (class "Default")
      (node (ref "IC6") (pin "5") (pinfunction "+IN_5") (pintype "input"))
      (node (ref "R24") (pin "2") (pinfunction "2_2") (pintype "passive"))
      (node (ref "R32") (pin "1") (pinfunction "1_1") (pintype "passive"))
      (node (ref "R35") (pin "2") (pinfunction "2_2") (pintype "passive"))
    )
    (net (code "42") (name "Net-(IC6B-OUT)") (class "Default")
      (node (ref "IC6") (pin "7") (pinfunction "OUT_7") (pintype "output"))
      (node (ref "Q16") (pin "1") (pinfunction "G_1") (pintype "passive"))
      (node (ref "R24") (pin "1") (pinfunction "1_1") (pintype "passive"))
    )
    (net (code "43") (name "Net-(Q3-D)") (class "Default")
      (node (ref "Q3") (pin "3") (pinfunction "D_3") (pintype "passive"))
      (node (ref "RELAY") (pin "2") (pinfunction "S_2") (pintype "passive"))
    )
    (net (code "44") (name "Net-(Q6-D)") (class "Default")
      (node (ref "Q6") (pin "3") (pinfunction "D_3") (pintype "passive"))
      (node (ref "RELAY") (pin "3") (pinfunction "S_3") (pintype "passive"))
    )
    (net (code "45") (name "Net-(Q7-G)") (class "Default")
      (node (ref "Q7") (pin "1") (pinfunction "G_1") (pintype "passive"))
      (node (ref "Q8") (pin "3") (pinfunction "D_3") (pintype "passive"))
      (node (ref "R17") (pin "2") (pinfunction "2_2") (pintype "passive"))
    )
    (net (code "46") (name "Net-(Q10-D)") (class "Default")
      (node (ref "Q10") (pin "3") (pinfunction "D_3") (pintype "passive"))
      (node (ref "Q5") (pin "3") (pinfunction "D_3") (pintype "passive"))
      (node (ref "SIREN") (pin "1") (pinfunction "KL_1") (pintype "passive"))
    )
    (net (code "47") (name "Net-(Q11-D)") (class "Default")
      (node (ref "Q11") (pin "3") (pinfunction "D_3") (pintype "passive"))
      (node (ref "RELAY") (pin "4") (pinfunction "S_4") (pintype "passive"))
    )
    (net (code "48") (name "Net-(Q12-D)") (class "Default")
      (node (ref "D5") (pin "A") (pinfunction "A_A") (pintype "passive"))
      (node (ref "Q12") (pin "3") (pinfunction "D_3") (pintype "passive"))
    )
    (net (code "49") (name "Net-(Q12-G)") (class "Default")
      (node (ref "Q12") (pin "1") (pinfunction "G_1") (pintype "passive"))
      (node (ref "Q13") (pin "3") (pinfunction "D_3") (pintype "passive"))
      (node (ref "R28") (pin "1") (pinfunction "1_1") (pintype "passive"))
    )
    (net (code "50") (name "Net-(Q14-D)") (class "Default")
      (node (ref "Q14") (pin "3") (pinfunction "D_3") (pintype "passive"))
      (node (ref "RELAY") (pin "5") (pinfunction "S_5") (pintype "passive"))
    )
    (net (code "51") (name "Net-(Q15-D)") (class "Default")
      (node (ref "D2") (pin "A") (pinfunction "A_A") (pintype "passive"))
      (node (ref "Q15") (pin "3") (pinfunction "D_3") (pintype "passive"))
      (node (ref "Q9") (pin "3") (pinfunction "D_3") (pintype "passive"))
    )
    (net (code "52") (name "Net-(R21-Pad2)") (class "Default")
      (node (ref "R21") (pin "2") (pinfunction "2_2") (pintype "passive"))
      (node (ref "R27") (pin "1") (pinfunction "1_1") (pintype "passive"))
    )
    (net (code "53") (name "Net-(R22-A)") (class "Default")
      (node (ref "R22") (pin "1") (pinfunction "A_1") (pintype "passive"))
      (node (ref "R25") (pin "2") (pinfunction "2_2") (pintype "passive"))
    )
    (net (code "54") (name "RE1") (class "Default")
      (node (ref "IC2") (pin "7") (pinfunction "P3_7") (pintype "bidirectional"))
      (node (ref "Q3") (pin "1") (pinfunction "G_1") (pintype "passive"))
      (node (ref "R1") (pin "2") (pinfunction "2_2") (pintype "passive"))
    )
    (net (code "55") (name "RE2") (class "Default")
      (node (ref "IC2") (pin "6") (pinfunction "P2_6") (pintype "bidirectional"))
      (node (ref "Q6") (pin "1") (pinfunction "G_1") (pintype "passive"))
      (node (ref "R4") (pin "2") (pinfunction "2_2") (pintype "passive"))
    )
    (net (code "56") (name "RE3") (class "Default")
      (node (ref "IC2") (pin "5") (pinfunction "P1_5") (pintype "bidirectional"))
      (node (ref "Q11") (pin "1") (pinfunction "G_1") (pintype "passive"))
      (node (ref "R2") (pin "2") (pinfunction "2_2") (pintype "passive"))
    )
    (net (code "57") (name "RE4") (class "Default")
      (node (ref "IC2") (pin "4") (pinfunction "P0_4") (pintype "bidirectional"))
      (node (ref "Q14") (pin "1") (pinfunction "G_1") (pintype "passive"))
      (node (ref "R5") (pin "2") (pinfunction "2_2") (pintype "passive"))
    )
    (net (code "58") (name "RZ") (class "Default")
      (node (ref "IC2") (pin "9") (pinfunction "P4_9") (pintype "bidirectional"))
      (node (ref "Q8") (pin "1") (pinfunction "G_1") (pintype "passive"))
      (node (ref "R18") (pin "2") (pinfunction "2_2") (pintype "passive"))
    )
    (net (code "59") (name "SBAT") (class "Default")
      (node (ref "Q16") (pin "3") (pinfunction "D_3") (pintype "passive"))
      (node (ref "R36") (pin "2") (pinfunction "2_2") (pintype "passive"))
    )
    (net (code "60") (name "SCL") (class "Default")
      (node (ref "I2C/1") (pin "3") (pinfunction "3_3") (pintype "passive"))
      (node (ref "IC2") (pin "14") (pinfunction "SCL_14") (pintype "input"))
      (node (ref "IC2/2") (pin "3") (pinfunction "3_3") (pintype "passive"))
      (node (ref "PROMINI69") (pin "A5") (pinfunction "A5/SCL_A5") (pintype "bidirectional"))
      (node (ref "R9") (pin "2") (pinfunction "2_2") (pintype "passive"))
    )
    (net (code "61") (name "SDA") (class "Default")
      (node (ref "I2C/1") (pin "4") (pinfunction "4_4") (pintype "passive"))
      (node (ref "IC2") (pin "15") (pinfunction "SDA_15") (pintype "bidirectional"))
      (node (ref "IC2/2") (pin "4") (pinfunction "4_4") (pintype "passive"))
      (node (ref "PROMINI69") (pin "A4") (pinfunction "A4/SDA_A4") (pintype "bidirectional"))
      (node (ref "R10") (pin "2") (pinfunction "2_2") (pintype "passive"))
    )
    (net (code "62") (name "SIR") (class "Default")
      (node (ref "PROMINI69") (pin "D6") (pinfunction "D6_D6") (pintype "bidirectional"))
      (node (ref "Q10") (pin "1") (pinfunction "G_1") (pintype "passive"))
      (node (ref "Q5") (pin "1") (pinfunction "G_1") (pintype "passive"))
      (node (ref "R3") (pin "2") (pinfunction "2_2") (pintype "passive"))
    )
    (net (code "63") (name "VBATR") (class "Default")
      (node (ref "IC6") (pin "1") (pinfunction "OUT_1") (pintype "output"))
      (node (ref "IC6") (pin "2") (pinfunction "-IN_2") (pintype "input"))
      (node (ref "PROMINI69") (pin "A6") (pinfunction "A6_A6") (pintype "bidirectional"))
    )
    (net (code "64") (name "VDD") (class "Default")
      (node (ref "C19") (pin "2") (pinfunction "2_2") (pintype "passive"))
      (node (ref "C2") (pin "+") (pinfunction "+_+") (pintype "passive"))
      (node (ref "D1") (pin "C") (pinfunction "C_C") (pintype "passive"))
      (node (ref "D2") (pin "C") (pinfunction "C_C") (pintype "passive"))
      (node (ref "IC1") (pin "3") (pinfunction "IN_3") (pintype "input"))
      (node (ref "IC1") (pin "4") (pinfunction "IN_4") (pintype "input"))
      (node (ref "J1") (pin "3") (pinfunction "3_3") (pintype "passive"))
      (node (ref "J2") (pin "3") (pinfunction "3_3") (pintype "passive"))
      (node (ref "J3") (pin "3") (pinfunction "3_3") (pintype "passive"))
      (node (ref "J6") (pin "3") (pinfunction "3_3") (pintype "passive"))
      (node (ref "PSMV1") (pin "2") (pinfunction "2_2") (pintype "passive"))
      (node (ref "PSMV1") (pin "3") (pinfunction "3_3") (pintype "passive"))
      (node (ref "PSMV2") (pin "2") (pinfunction "2_2") (pintype "passive"))
      (node (ref "PSMV2") (pin "3") (pinfunction "3_3") (pintype "passive"))
      (node (ref "PSMV3") (pin "2") (pinfunction "2_2") (pintype "passive"))
      (node (ref "PSMV3") (pin "3") (pinfunction "3_3") (pintype "passive"))
      (node (ref "SIREN") (pin "2") (pinfunction "KL_2") (pintype "passive"))
    )
    (net (code "65") (name "unconnected-(IC2-~{INT}-Pad13)") (class "Default")
      (node (ref "IC2") (pin "13") (pinfunction "~{INT}_13") (pintype "output"))
    )
    (net (code "66") (name "unconnected-(PROMINI69-PadD2)") (class "Default")
      (node (ref "PROMINI69") (pin "D2") (pinfunction "D2_D2") (pintype "bidirectional"))
    )
    (net (code "67") (name "unconnected-(PROMINI69-PadD8)") (class "Default")
      (node (ref "PROMINI69") (pin "D8") (pinfunction "D8_D8") (pintype "bidirectional"))
    )
    (net (code "68") (name "unconnected-(PROMINI69-PadD11)") (class "Default")
      (node (ref "PROMINI69") (pin "D11") (pinfunction "D11_D11") (pintype "bidirectional"))
    )
    (net (code "69") (name "unconnected-(PROMINI69-PadD12)") (class "Default")
      (node (ref "PROMINI69") (pin "D12") (pinfunction "D12_D12") (pintype "bidirectional"))
    )
    (net (code "70") (name "unconnected-(PROMINI69-PadD13)") (class "Default")
      (node (ref "PROMINI69") (pin "D13") (pinfunction "D13_D13") (pintype "bidirectional"))
    )
    (net (code "71") (name "unconnected-(PROMINI69-PadRST)") (class "Default")
      (node (ref "PROMINI69") (pin "RST") (pinfunction "RST_RST") (pintype "bidirectional"))
    )
  )
)
